# 3_3_Buck.net
KiCad netlist of a schematic drawn in Altium Designer
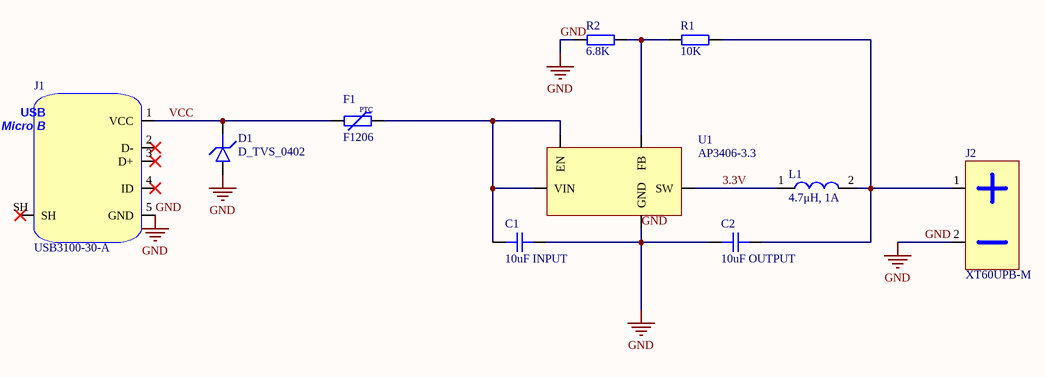
[diagram p0: 3.3 Buck.SchDoc]

(export (version "E")
  (design (tool "Eeschema 10.0.6"))
  (components
    (comp (ref "C1")
      (value "10uF INPUT")
      (footprint "CAP_0805")
      (description "Capacitor SMD 0805")
      (libsource (lib "Schematic-Lib-PhilsLab") (part "CAP_0805"))
    )
    (comp (ref "C2")
      (value "10uF OUTPUT")
      (footprint "CAP_0805")
      (description "Capacitor SMD 0805")
      (libsource (lib "Schematic-Lib-PhilsLab") (part "CAP_0805"))
    )
    (comp (ref "D1")
      (value "D_TVS_0402")
      (footprint "D_0402")
      (description "Diode TVS / ESD 0402")
      (libsource (lib "Schematic-Lib-PhilsLab") (part "D_TVS_0402"))
    )
    (comp (ref "F1")
      (value "F1206")
      (footprint "FUSE_1206")
      (description "Fuse PPTC SMD 1206")
      (libsource (lib "Schematic-Lib-PhilsLab") (part "FUSE_PPTC_1206"))
    )
    (comp (ref "J1")
      (value "USB3100-30-A")
      (footprint "USB3100-30-A")
      (description "USB Connector Type Micro B 2.0 SMD Reverse Mount")
      (fields (field (name "MANUFACTURER") "GCT"))
      (libsource (lib "Schematic-Lib-PhilsLab") (part "USB3100-30-A"))
    )
    (comp (ref "J2")
      (value "XT60UPB-M")
      (footprint "XT60UPB-M")
      (description "XT60 vertical male 2-pin AMASS")
      (fields (field (name "MANUFACTURER") "AMASS"))
      (libsource (lib "Schematic-Lib-PhilsLab") (part "XT60UPB-M"))
    )
    (comp (ref "L1")
      (value "4.7μH, 1A")
      (footprint "4.7µH, 1A")
      (description "FIXED IND 4.7UH 0.88A 156MOHM")
      (fields
        (field (name "MANUFACTURER") "Murata")
        (field (name "MANUFACTURER PART NUMBER") "LQH3NPN4R7MM0L")
      )
      (libsource (lib "3.3 Buck") (part "LQH3NPN4R7MM0L"))
    )
    (comp (ref "R1")
      (value "10K")
      (footprint "RES_0805")
      (description "Resistor SMD 0805")
      (libsource (lib "Schematic-Lib-PhilsLab") (part "RES_0805"))
    )
    (comp (ref "R2")
      (value "6.8K")
      (footprint "RES_0805")
      (description "Resistor SMD 0805")
      (libsource (lib "Schematic-Lib-PhilsLab") (part "RES_0805"))
    )
    (comp (ref "U1") (value "AP3406-3.3") (footprint "SOT-23") (libsource (lib "3.3 Buck") (part "AP3406KT")))
  )
  (nets
    (net (code "1") (name "/3.3V") (class "Default")
      (node (ref "L1") (pin "1") (pinfunction "1_1") (pintype "passive"))
      (node (ref "U1") (pin "3") (pinfunction "SW_3") (pintype "passive"))
    )
    (net (code "2") (name "/VCC") (class "Default")
      (node (ref "D1") (pin "K") (pinfunction "K_K") (pintype "passive"))
      (node (ref "F1") (pin "1") (pinfunction "1_1") (pintype "passive"))
      (node (ref "J1") (pin "1") (pinfunction "VCC_1") (pintype "passive"))
    )
    (net (code "3") (name "GND") (class "Default")
      (node (ref "C1") (pin "2") (pinfunction "2_2") (pintype "passive"))
      (node (ref "C2") (pin "1") (pinfunction "1_1") (pintype "passive"))
      (node (ref "D1") (pin "A") (pinfunction "A_A") (pintype "passive"))
      (node (ref "J1") (pin "5") (pinfunction "GND_5") (pintype "passive"))
      (node (ref "J2") (pin "2") (pinfunction "V-_2") (pintype "power_in"))
      (node (ref "R2") (pin "1") (pinfunction "1_1") (pintype "passive"))
      (node (ref "U1") (pin "2") (pinfunction "GND_2") (pintype "passive"))
    )
    (net (code "4") (name "Net-(J2-V+)") (class "Default")
      (node (ref "C2") (pin "2") (pinfunction "2_2") (pintype "passive"))
      (node (ref "J2") (pin "1") (pinfunction "V+_1") (pintype "power_in"))
      (node (ref "L1") (pin "2") (pinfunction "2_2") (pintype "passive"))
      (node (ref "R1") (pin "2") (pinfunction "2_2") (pintype "passive"))
    )
    (net (code "5") (name "Net-(U1-EN)") (class "Default")
      (node (ref "C1") (pin "1") (pinfunction "1_1") (pintype "passive"))
      (node (ref "F1") (pin "2") (pinfunction "2_2") (pintype "passive"))
      (node (ref "U1") (pin "1") (pinfunction "EN_1") (pintype "passive"))
      (node (ref "U1") (pin "4") (pinfunction "VIN_4") (pintype "passive"))
    )
    (net (code "6") (name "Net-(U1-FB)") (class "Default")
      (node (ref "R1") (pin "1") (pinfunction "1_1") (pintype "passive"))
      (node (ref "R2") (pin "2") (pinfunction "2_2") (pintype "passive"))
      (node (ref "U1") (pin "5") (pinfunction "FB_5") (pintype "passive"))
    )
    (net (code "7") (name "unconnected-(J1-D+-Pad3)") (class "Default")
      (node (ref "J1") (pin "3") (pinfunction "D+_3") (pintype "passive+no_connect"))
    )
    (net (code "8") (name "unconnected-(J1-D--Pad2)") (class "Default")
      (node (ref "J1") (pin "2") (pinfunction "D-_2") (pintype "passive+no_connect"))
    )
    (net (code "9") (name "unconnected-(J1-ID-Pad4)") (class "Default")
      (node (ref "J1") (pin "4") (pinfunction "ID_4") (pintype "passive+no_connect"))
    )
    (net (code "10") (name "unconnected-(J1-PadSH)") (class "Default")
      (node (ref "J1") (pin "SH") (pinfunction "SH_SH") (pintype "passive+no_connect"))
    )
  )
)
